# rgb_v3.net
KiCad netlist of a schematic drawn in EAGLE
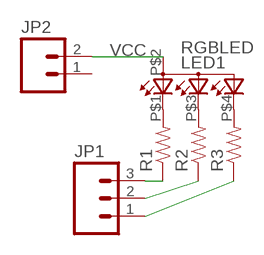
[diagram p0: schematic, sheet 1]

(export (version "E")
  (design (tool "Eeschema 10.0.6"))
  (components
    (comp (ref "JP1")
      (value "M03NONPOLAR")
      (footprint "eagle-import:1X03NONPOLAR")
      (libsource (lib "eagle-import") (part "M03NONPOLAR"))
    )
    (comp (ref "JP2")
      (value "M02PTH")
      (footprint "eagle-import:1X02")
      (libsource (lib "eagle-import") (part "M02PTH"))
    )
    (comp (ref "LED1")
      (value "RGBLED")
      (footprint "eagle-import:CLVBA-FKA-CAEDH8BBB7A363")
      (libsource (lib "eagle-import") (part "RGBLED"))
    )
    (comp (ref "R1")
      (value "RESISTOR0402-RES")
      (footprint "eagle-import:0402-RES")
      (libsource (lib "eagle-import") (part "RESISTOR0402-RES"))
    )
    (comp (ref "R2")
      (value "RESISTOR0402-RES")
      (footprint "eagle-import:0402-RES")
      (libsource (lib "eagle-import") (part "RESISTOR0402-RES"))
    )
    (comp (ref "R3")
      (value "RESISTOR0402-RES")
      (footprint "eagle-import:0402-RES")
      (libsource (lib "eagle-import") (part "RESISTOR0402-RES"))
    )
  )
  (nets
    (net (code "1") (name "/VCC") (class "Default")
      (node (ref "JP2") (pin "2") (pinfunction "2_2") (pintype "passive"))
      (node (ref "LED1") (pin "P$2") (pinfunction "A_P$2") (pintype "passive"))
    )
    (net (code "2") (name "Net-(JP1-Pad1)") (class "Default")
      (node (ref "JP1") (pin "1") (pinfunction "1_1") (pintype "passive"))
      (node (ref "R3") (pin "1") (pinfunction "1_1") (pintype "passive"))
    )
    (net (code "3") (name "Net-(JP1-Pad2)") (class "Default")
      (node (ref "JP1") (pin "2") (pinfunction "2_2") (pintype "passive"))
      (node (ref "R2") (pin "1") (pinfunction "1_1") (pintype "passive"))
    )
    (net (code "4") (name "Net-(JP1-Pad3)") (class "Default")
      (node (ref "JP1") (pin "3") (pinfunction "3_3") (pintype "passive"))
      (node (ref "R1") (pin "1") (pinfunction "1_1") (pintype "passive"))
    )
    (net (code "5") (name "Net-(LED1-CBLUE)") (class "Default")
      (node (ref "LED1") (pin "P$3") (pinfunction "CBLUE_P$3") (pintype "passive"))
      (node (ref "R2") (pin "2") (pinfunction "2_2") (pintype "passive"))
    )
    (net (code "6") (name "Net-(LED1-CGREEN)") (class "Default")
      (node (ref "LED1") (pin "P$4") (pinfunction "CGREEN_P$4") (pintype "passive"))
      (node (ref "R3") (pin "2") (pinfunction "2_2") (pintype "passive"))
    )
    (net (code "7") (name "Net-(LED1-CRED)") (class "Default")
      (node (ref "LED1") (pin "P$1") (pinfunction "CRED_P$1") (pintype "passive"))
      (node (ref "R1") (pin "2") (pinfunction "2_2") (pintype "passive"))
    )
    (net (code "8") (name "unconnected-(JP2-Pad1)") (class "Default")
      (node (ref "JP2") (pin "1") (pinfunction "1_1") (pintype "passive"))
    )
  )
)
